# RPi_BUS-Controller_V1_0.net
KiCad netlist of a schematic drawn in EAGLE
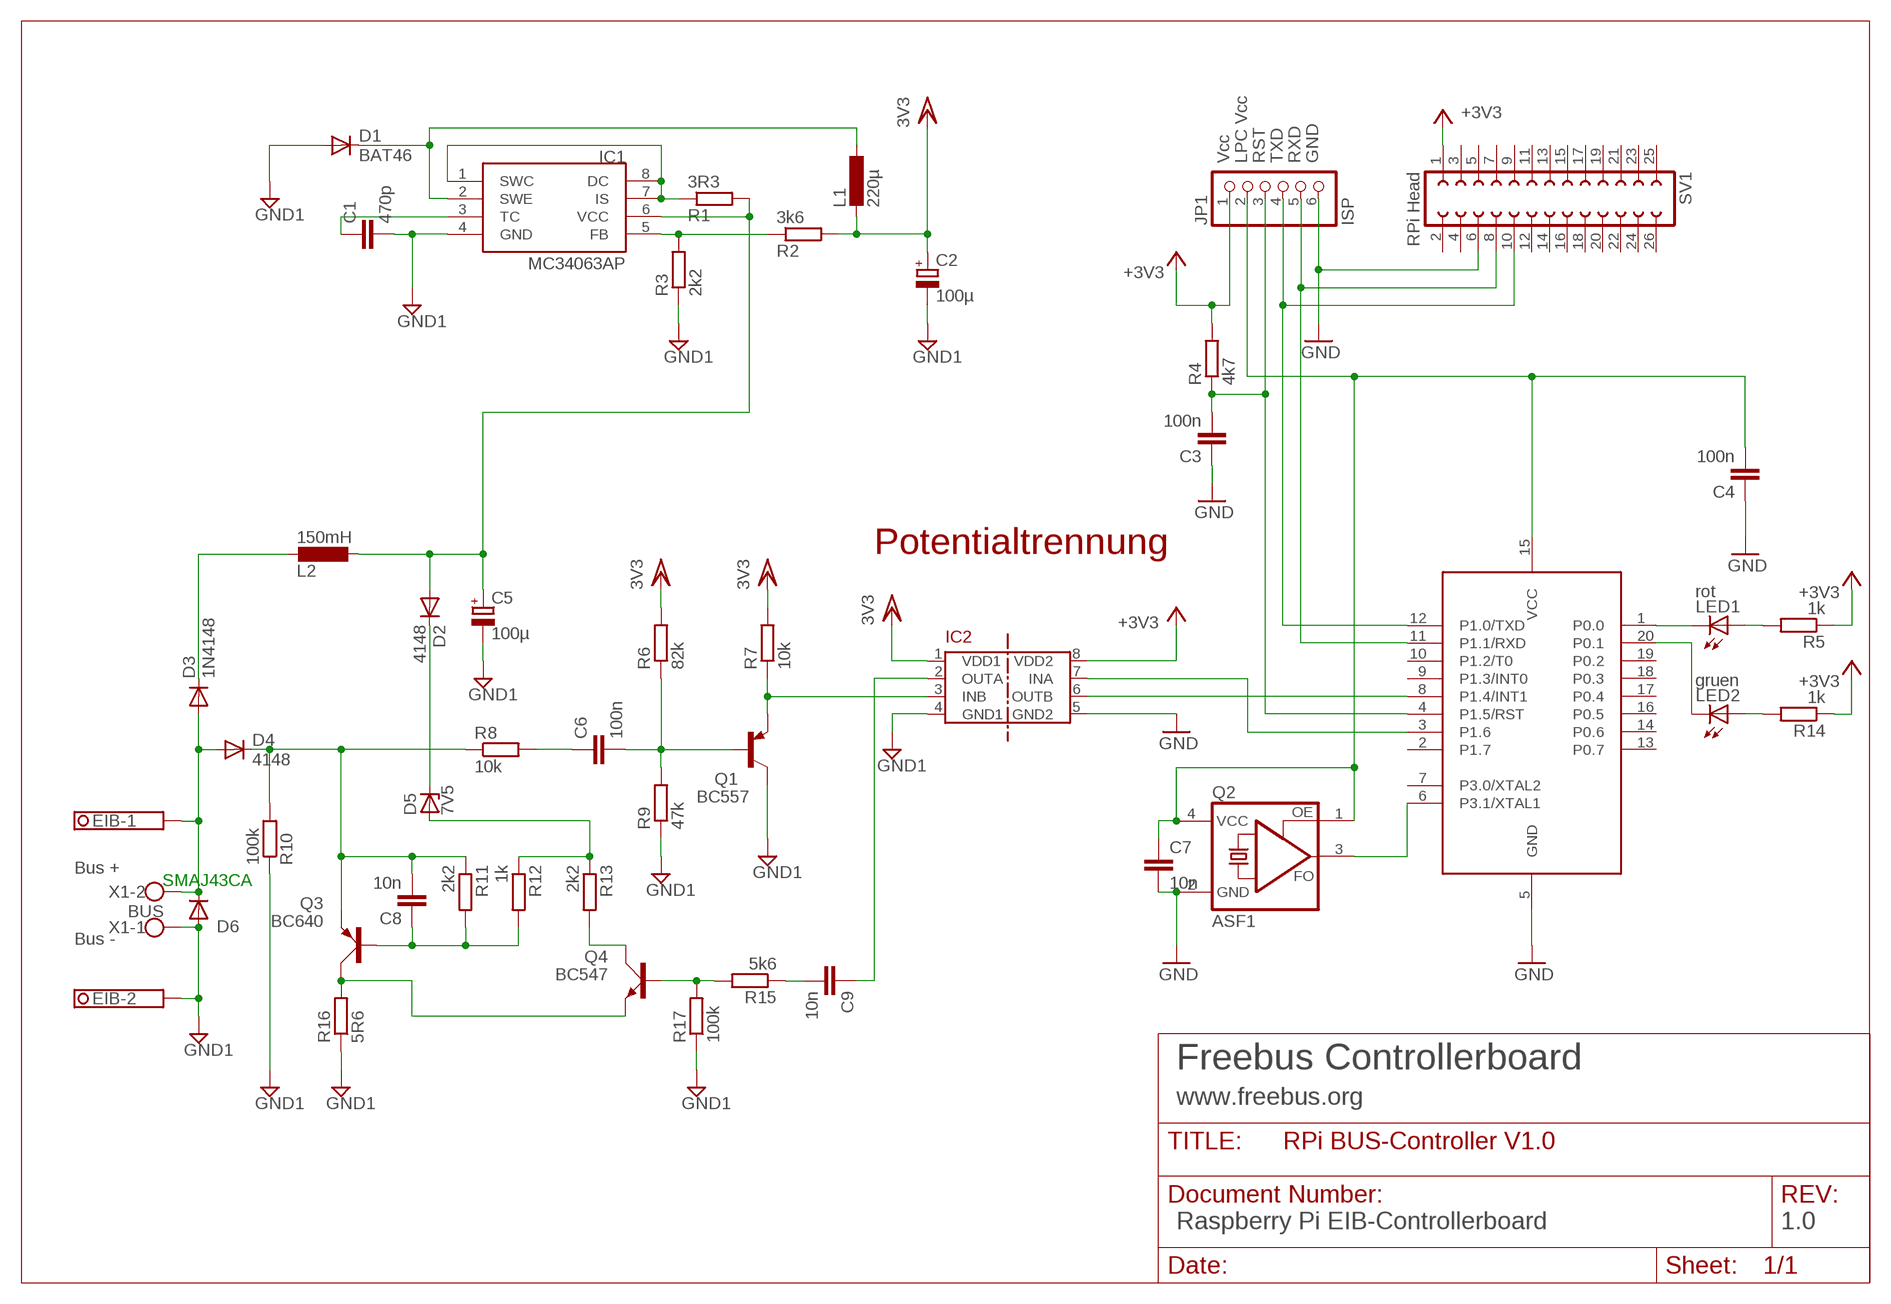
[diagram p0: schematic, sheet 1]

(export (version "E")
  (design (tool "Eeschema 10.0.6"))
  (components
    (comp (ref "C1")
      (value "470p")
      (footprint "eagle-import:C025-024X044")
      (libsource (lib "eagle-import") (part "C-EU025-024X044"))
    )
    (comp (ref "C2")
      (value "100µ")
      (footprint "eagle-import:2-5X11")
      (libsource (lib "eagle-import") (part "RCL_C_EU_H2-5X11"))
    )
    (comp (ref "C3")
      (value "100n")
      (footprint "eagle-import:C025-024X044")
      (libsource (lib "eagle-import") (part "C-EU025-024X044"))
    )
    (comp (ref "C4")
      (value "100n")
      (footprint "eagle-import:C025-024X044")
      (libsource (lib "eagle-import") (part "C-EU025-024X044"))
    )
    (comp (ref "C5")
      (value "100µ")
      (footprint "eagle-import:3,5-8X13")
      (libsource (lib "eagle-import") (part "RCL_C_EU_H3,5-8X13"))
    )
    (comp (ref "C6")
      (value "100n")
      (footprint "eagle-import:C025-024X044")
      (libsource (lib "eagle-import") (part "C-EU025-024X044"))
    )
    (comp (ref "C7")
      (value "10n")
      (footprint "eagle-import:C025-024X044")
      (libsource (lib "eagle-import") (part "C-EU025-024X044"))
    )
    (comp (ref "C8")
      (value "10n")
      (footprint "eagle-import:C025-024X044")
      (libsource (lib "eagle-import") (part "C-EU025-024X044"))
    )
    (comp (ref "C9")
      (value "10n")
      (footprint "eagle-import:C025-024X044")
      (libsource (lib "eagle-import") (part "C-EU025-024X044"))
    )
    (comp (ref "D1")
      (value "BAT46")
      (footprint "eagle-import:DO35-7")
      (libsource (lib "eagle-import") (part "1N4148DO35-7"))
    )
    (comp (ref "D2")
      (value "4148")
      (footprint "eagle-import:DO35-7")
      (libsource (lib "eagle-import") (part "1N4148DO35-7"))
    )
    (comp (ref "D3")
      (value "1N4148")
      (footprint "eagle-import:DO35-7")
      (libsource (lib "eagle-import") (part "1N4148DO35-7"))
    )
    (comp (ref "D4")
      (value "4148")
      (footprint "eagle-import:DO35-7")
      (libsource (lib "eagle-import") (part "1N4148DO35-7"))
    )
    (comp (ref "D5")
      (value "7V5")
      (footprint "eagle-import:DO35Z7")
      (libsource (lib "eagle-import") (part "ZPD{dblquote}"))
    )
    (comp (ref "D6")
      (value "SMAJ43CA")
      (footprint "eagle-import:SMB")
      (libsource (lib "eagle-import") (part "D-SMB"))
    )
    (comp (ref "EIB")
      (value "1751248")
      (footprint "eagle-import:1751248")
      (libsource (lib "eagle-import") (part "1751248"))
    )
    (comp (ref "IC1")
      (value "MC34063AP")
      (footprint "eagle-import:DIL08")
      (libsource (lib "eagle-import") (part "MC34063AP"))
    )
    (comp (ref "IC2")
      (value "ADUM1201")
      (footprint "eagle-import:SO8")
      (libsource (lib "eagle-import") (part "ADUM1201"))
    )
    (comp (ref "IC3")
      (value "89LPC922")
      (footprint "eagle-import:DIL20")
      (libsource (lib "eagle-import") (part "89LPC922"))
    )
    (comp (ref "JP1")
      (value "ISP")
      (footprint "eagle-import:1X06")
      (libsource (lib "eagle-import") (part "PINHD-1X6"))
    )
    (comp (ref "L1")
      (value "220µ")
      (footprint "eagle-import:0207_12")
      (libsource (lib "eagle-import") (part "L-EU0207/12"))
    )
    (comp (ref "L2")
      (value "150mH")
      (footprint "eagle-import:RCL_11PH")
      (libsource (lib "eagle-import") (part "RCL_L-11P11PH"))
    )
    (comp (ref "LED1")
      (value "rot")
      (footprint "eagle-import:LED3MM")
      (libsource (lib "eagle-import") (part "LED3MM"))
    )
    (comp (ref "LED2")
      (value "gruen")
      (footprint "eagle-import:LED3MM")
      (libsource (lib "eagle-import") (part "LED3MM"))
    )
    (comp (ref "Q1")
      (value "BC557")
      (footprint "eagle-import:TO92")
      (libsource (lib "eagle-import") (part "BC557"))
    )
    (comp (ref "Q2")
      (value "ASF1")
      (footprint "eagle-import:ASF")
      (libsource (lib "eagle-import") (part "ASF1"))
    )
    (comp (ref "Q3")
      (value "BC640")
      (footprint "eagle-import:SOT54D")
      (libsource (lib "eagle-import") (part "BC640"))
    )
    (comp (ref "Q4")
      (value "BC547")
      (footprint "eagle-import:SOT54A")
      (libsource (lib "eagle-import") (part "BC547"))
    )
    (comp (ref "R1")
      (value "3R3")
      (footprint "eagle-import:0207_7")
      (libsource (lib "eagle-import") (part "R-EU_0207/7"))
    )
    (comp (ref "R2")
      (value "3k6")
      (footprint "eagle-import:0207_7")
      (libsource (lib "eagle-import") (part "R-EU_0207/7"))
    )
    (comp (ref "R3")
      (value "2k2")
      (footprint "eagle-import:0207_7")
      (libsource (lib "eagle-import") (part "R-EU_0207/7"))
    )
    (comp (ref "R4")
      (value "4k7")
      (footprint "eagle-import:0207_7")
      (libsource (lib "eagle-import") (part "R-EU_0207/7"))
    )
    (comp (ref "R5")
      (value "1k")
      (footprint "eagle-import:0207_7")
      (libsource (lib "eagle-import") (part "R-EU_0207/7"))
    )
    (comp (ref "R6")
      (value "82k")
      (footprint "eagle-import:0207_7")
      (libsource (lib "eagle-import") (part "R-EU_0207/7"))
    )
    (comp (ref "R7")
      (value "10k")
      (footprint "eagle-import:0207_7")
      (libsource (lib "eagle-import") (part "R-EU_0207/7"))
    )
    (comp (ref "R8")
      (value "10k")
      (footprint "eagle-import:0207_7")
      (libsource (lib "eagle-import") (part "R-EU_0207/7"))
    )
    (comp (ref "R9")
      (value "47k")
      (footprint "eagle-import:0207_7")
      (libsource (lib "eagle-import") (part "R-EU_0207/7"))
    )
    (comp (ref "R10")
      (value "100k")
      (footprint "eagle-import:0207_7")
      (libsource (lib "eagle-import") (part "R-EU_0207/7"))
    )
    (comp (ref "R11")
      (value "2k2")
      (footprint "eagle-import:0207_7")
      (libsource (lib "eagle-import") (part "R-EU_0207/7"))
    )
    (comp (ref "R12")
      (value "1k")
      (footprint "eagle-import:0207_7")
      (libsource (lib "eagle-import") (part "R-EU_0207/7"))
    )
    (comp (ref "R13")
      (value "2k2")
      (footprint "eagle-import:0207_7")
      (libsource (lib "eagle-import") (part "R-EU_0207/7"))
    )
    (comp (ref "R14")
      (value "1k")
      (footprint "eagle-import:0207_7")
      (libsource (lib "eagle-import") (part "R-EU_0207/7"))
    )
    (comp (ref "R15")
      (value "5k6")
      (footprint "eagle-import:0207_7")
      (libsource (lib "eagle-import") (part "R-EU_0207/7"))
    )
    (comp (ref "R16")
      (value "5R6")
      (footprint "eagle-import:0207_7")
      (libsource (lib "eagle-import") (part "R-EU_0207/7"))
    )
    (comp (ref "R17")
      (value "100k")
      (footprint "eagle-import:0207_7")
      (libsource (lib "eagle-import") (part "R-EU_0207/7"))
    )
    (comp (ref "SV1")
      (value "RPi Head")
      (footprint "eagle-import:FE13-2")
      (libsource (lib "eagle-import") (part "FE13-2"))
    )
    (comp (ref "X1")
      (value "BUS")
      (footprint "eagle-import:W237-132")
      (libsource (lib "eagle-import") (part "W237-02P"))
    )
  )
  (nets
    (net (code "1") (name "+3V3") (class "Default")
      (node (ref "IC2") (pin "8") (pinfunction "VDD2_8") (pintype "power_in"))
      (node (ref "JP1") (pin "1") (pinfunction "1_1") (pintype "passive"))
      (node (ref "R14") (pin "1") (pinfunction "1_1") (pintype "passive"))
      (node (ref "R4") (pin "2") (pinfunction "2_2") (pintype "passive"))
      (node (ref "R5") (pin "1") (pinfunction "1_1") (pintype "passive"))
      (node (ref "SV1") (pin "1") (pinfunction "1_1") (pintype "passive"))
    )
    (net (code "2") (name "3V3") (class "Default")
      (node (ref "C2") (pin "+") (pinfunction "+_+") (pintype "passive"))
      (node (ref "IC2") (pin "1") (pinfunction "VDD1_1") (pintype "power_in"))
      (node (ref "L1") (pin "2") (pinfunction "2_2") (pintype "passive"))
      (node (ref "R2") (pin "2") (pinfunction "2_2") (pintype "passive"))
      (node (ref "R6") (pin "2") (pinfunction "2_2") (pintype "passive"))
      (node (ref "R7") (pin "2") (pinfunction "2_2") (pintype "passive"))
    )
    (net (code "3") (name "GND") (class "Default")
      (node (ref "C3") (pin "1") (pinfunction "1_1") (pintype "passive"))
      (node (ref "C4") (pin "1") (pinfunction "1_1") (pintype "passive"))
      (node (ref "C7") (pin "2") (pinfunction "2_2") (pintype "passive"))
      (node (ref "IC2") (pin "5") (pinfunction "GND2_5") (pintype "power_in"))
      (node (ref "IC3") (pin "5") (pinfunction "GND_5") (pintype "bidirectional"))
      (node (ref "JP1") (pin "6") (pinfunction "6_6") (pintype "passive"))
      (node (ref "Q2") (pin "2") (pinfunction "GND_2") (pintype "power_in"))
      (node (ref "SV1") (pin "6") (pinfunction "6_6") (pintype "passive"))
    )
    (net (code "4") (name "GND1") (class "Default")
      (node (ref "C1") (pin "2") (pinfunction "2_2") (pintype "passive"))
      (node (ref "C2") (pin "-") (pinfunction "-_-") (pintype "passive"))
      (node (ref "C5") (pin "-") (pinfunction "-_-") (pintype "passive"))
      (node (ref "D1") (pin "A") (pinfunction "A_A") (pintype "passive"))
      (node (ref "D6") (pin "2") (pinfunction "A_2") (pintype "passive"))
      (node (ref "EIB") (pin "2") (pinfunction "K_2") (pintype "passive"))
      (node (ref "IC1") (pin "4") (pinfunction "GND_4") (pintype "passive"))
      (node (ref "IC2") (pin "4") (pinfunction "GND1_4") (pintype "power_in"))
      (node (ref "Q1") (pin "3") (pinfunction "C_3") (pintype "passive"))
      (node (ref "R10") (pin "1") (pinfunction "1_1") (pintype "passive"))
      (node (ref "R16") (pin "1") (pinfunction "1_1") (pintype "passive"))
      (node (ref "R17") (pin "1") (pinfunction "1_1") (pintype "passive"))
      (node (ref "R3") (pin "1") (pinfunction "1_1") (pintype "passive"))
      (node (ref "R9") (pin "1") (pinfunction "1_1") (pintype "passive"))
      (node (ref "X1") (pin "1") (pinfunction "KL_1") (pintype "passive"))
    )
    (net (code "5") (name "Net-(C6-Pad1)") (class "Default")
      (node (ref "C6") (pin "1") (pinfunction "1_1") (pintype "passive"))
      (node (ref "R8") (pin "2") (pinfunction "2_2") (pintype "passive"))
    )
    (net (code "6") (name "Net-(C8-Pad1)") (class "Default")
      (node (ref "C8") (pin "1") (pinfunction "1_1") (pintype "passive"))
      (node (ref "Q3") (pin "B") (pinfunction "B_B") (pintype "passive"))
      (node (ref "R11") (pin "2") (pinfunction "2_2") (pintype "passive"))
      (node (ref "R12") (pin "2") (pinfunction "2_2") (pintype "passive"))
    )
    (net (code "7") (name "Net-(C8-Pad2)") (class "Default")
      (node (ref "C8") (pin "2") (pinfunction "2_2") (pintype "passive"))
      (node (ref "D4") (pin "C") (pinfunction "C_C") (pintype "passive"))
      (node (ref "Q3") (pin "E") (pinfunction "E_E") (pintype "passive"))
      (node (ref "R10") (pin "2") (pinfunction "2_2") (pintype "passive"))
      (node (ref "R11") (pin "1") (pinfunction "1_1") (pintype "passive"))
      (node (ref "R8") (pin "1") (pinfunction "1_1") (pintype "passive"))
    )
    (net (code "8") (name "Net-(C9-Pad2)") (class "Default")
      (node (ref "C9") (pin "2") (pinfunction "2_2") (pintype "passive"))
      (node (ref "R15") (pin "1") (pinfunction "1_1") (pintype "passive"))
    )
    (net (code "9") (name "Net-(D2-PadC)") (class "Default")
      (node (ref "D2") (pin "C") (pinfunction "C_C") (pintype "passive"))
      (node (ref "D5") (pin "C") (pinfunction "C_C") (pintype "passive"))
    )
    (net (code "10") (name "Net-(D5-PadA)") (class "Default")
      (node (ref "D5") (pin "A") (pinfunction "A_A") (pintype "passive"))
      (node (ref "R12") (pin "1") (pinfunction "1_1") (pintype "passive"))
      (node (ref "R13") (pin "1") (pinfunction "1_1") (pintype "passive"))
    )
    (net (code "11") (name "Net-(D6-C)") (class "Default")
      (node (ref "D3") (pin "A") (pinfunction "A_A") (pintype "passive"))
      (node (ref "D4") (pin "A") (pinfunction "A_A") (pintype "passive"))
      (node (ref "D6") (pin "1") (pinfunction "C_1") (pintype "passive"))
      (node (ref "EIB") (pin "1") (pinfunction "K_1") (pintype "passive"))
      (node (ref "X1") (pin "2") (pinfunction "KL_2") (pintype "passive"))
    )
    (net (code "12") (name "Net-(IC1-DC)") (class "Default")
      (node (ref "IC1") (pin "1") (pinfunction "SWC_1") (pintype "passive"))
      (node (ref "IC1") (pin "7") (pinfunction "IS_7") (pintype "passive"))
      (node (ref "IC1") (pin "8") (pinfunction "DC_8") (pintype "passive"))
      (node (ref "R1") (pin "1") (pinfunction "1_1") (pintype "passive"))
    )
    (net (code "13") (name "Net-(IC1-FB)") (class "Default")
      (node (ref "IC1") (pin "5") (pinfunction "FB_5") (pintype "passive"))
      (node (ref "R2") (pin "1") (pinfunction "1_1") (pintype "passive"))
      (node (ref "R3") (pin "2") (pinfunction "2_2") (pintype "passive"))
    )
    (net (code "14") (name "Net-(IC1-SWE)") (class "Default")
      (node (ref "D1") (pin "C") (pinfunction "C_C") (pintype "passive"))
      (node (ref "IC1") (pin "2") (pinfunction "SWE_2") (pintype "passive"))
      (node (ref "L1") (pin "1") (pinfunction "1_1") (pintype "passive"))
    )
    (net (code "15") (name "Net-(IC1-TC)") (class "Default")
      (node (ref "C1") (pin "1") (pinfunction "1_1") (pintype "passive"))
      (node (ref "IC1") (pin "3") (pinfunction "TC_3") (pintype "passive"))
    )
    (net (code "16") (name "Net-(IC1-VCC)") (class "Default")
      (node (ref "C5") (pin "+") (pinfunction "+_+") (pintype "passive"))
      (node (ref "D2") (pin "A") (pinfunction "A_A") (pintype "passive"))
      (node (ref "IC1") (pin "6") (pinfunction "VCC_6") (pintype "passive"))
      (node (ref "L2") (pin "P$1") (pinfunction "1_P$1") (pintype "passive"))
      (node (ref "R1") (pin "2") (pinfunction "2_2") (pintype "passive"))
    )
    (net (code "17") (name "Net-(IC2-INA)") (class "Default")
      (node (ref "IC2") (pin "7") (pinfunction "INA_7") (pintype "input"))
      (node (ref "IC3") (pin "3") (pinfunction "P1.6_3") (pintype "bidirectional"))
    )
    (net (code "18") (name "Net-(IC2-INB)") (class "Default")
      (node (ref "IC2") (pin "3") (pinfunction "INB_3") (pintype "input"))
      (node (ref "Q1") (pin "1") (pinfunction "E_1") (pintype "passive"))
      (node (ref "R7") (pin "1") (pinfunction "1_1") (pintype "passive"))
    )
    (net (code "19") (name "Net-(IC2-OUTA)") (class "Default")
      (node (ref "C9") (pin "1") (pinfunction "1_1") (pintype "passive"))
      (node (ref "IC2") (pin "2") (pinfunction "OUTA_2") (pintype "output"))
    )
    (net (code "20") (name "Net-(IC2-OUTB)") (class "Default")
      (node (ref "IC2") (pin "6") (pinfunction "OUTB_6") (pintype "output"))
      (node (ref "IC3") (pin "8") (pinfunction "P1.4/INT1_8") (pintype "bidirectional"))
    )
    (net (code "21") (name "Net-(IC3-P0.0)") (class "Default")
      (node (ref "IC3") (pin "1") (pinfunction "P0.0_1") (pintype "bidirectional"))
      (node (ref "LED1") (pin "K") (pinfunction "C_K") (pintype "passive"))
    )
    (net (code "22") (name "Net-(IC3-P0.1)") (class "Default")
      (node (ref "IC3") (pin "20") (pinfunction "P0.1_20") (pintype "bidirectional"))
      (node (ref "LED2") (pin "K") (pinfunction "C_K") (pintype "passive"))
    )
    (net (code "23") (name "Net-(IC3-P1.0{slash}TXD)") (class "Default")
      (node (ref "IC3") (pin "12") (pinfunction "P1.0/TXD_12") (pintype "bidirectional"))
      (node (ref "JP1") (pin "4") (pinfunction "4_4") (pintype "passive"))
      (node (ref "SV1") (pin "10") (pinfunction "10_10") (pintype "passive"))
    )
    (net (code "24") (name "Net-(IC3-P1.1{slash}RXD)") (class "Default")
      (node (ref "IC3") (pin "11") (pinfunction "P1.1/RXD_11") (pintype "bidirectional"))
      (node (ref "JP1") (pin "5") (pinfunction "5_5") (pintype "passive"))
      (node (ref "SV1") (pin "8") (pinfunction "8_8") (pintype "passive"))
    )
    (net (code "25") (name "Net-(IC3-P1.5{slash}RST)") (class "Default")
      (node (ref "C3") (pin "2") (pinfunction "2_2") (pintype "passive"))
      (node (ref "IC3") (pin "4") (pinfunction "P1.5/RST_4") (pintype "bidirectional"))
      (node (ref "JP1") (pin "3") (pinfunction "3_3") (pintype "passive"))
      (node (ref "R4") (pin "1") (pinfunction "1_1") (pintype "passive"))
    )
    (net (code "26") (name "Net-(IC3-P3.1{slash}XTAL1)") (class "Default")
      (node (ref "IC3") (pin "6") (pinfunction "P3.1/XTAL1_6") (pintype "bidirectional"))
      (node (ref "Q2") (pin "3") (pinfunction "FO_3") (pintype "output"))
    )
    (net (code "27") (name "Net-(IC3-VCC)") (class "Default")
      (node (ref "C4") (pin "2") (pinfunction "2_2") (pintype "passive"))
      (node (ref "C7") (pin "1") (pinfunction "1_1") (pintype "passive"))
      (node (ref "IC3") (pin "15") (pinfunction "VCC_15") (pintype "bidirectional"))
      (node (ref "JP1") (pin "2") (pinfunction "2_2") (pintype "passive"))
      (node (ref "Q2") (pin "1") (pinfunction "OE_1") (pintype "input"))
      (node (ref "Q2") (pin "4") (pinfunction "VCC_4") (pintype "power_in"))
    )
    (net (code "28") (name "Net-(L2-2)") (class "Default")
      (node (ref "D3") (pin "C") (pinfunction "C_C") (pintype "passive"))
      (node (ref "L2") (pin "P$2") (pinfunction "2_P$2") (pintype "passive"))
    )
    (net (code "29") (name "Net-(LED1-PadA)") (class "Default")
      (node (ref "LED1") (pin "A") (pinfunction "A_A") (pintype "passive"))
      (node (ref "R5") (pin "2") (pinfunction "2_2") (pintype "passive"))
    )
    (net (code "30") (name "Net-(LED2-PadA)") (class "Default")
      (node (ref "LED2") (pin "A") (pinfunction "A_A") (pintype "passive"))
      (node (ref "R14") (pin "2") (pinfunction "2_2") (pintype "passive"))
    )
    (net (code "31") (name "Net-(Q1-B)") (class "Default")
      (node (ref "C6") (pin "2") (pinfunction "2_2") (pintype "passive"))
      (node (ref "Q1") (pin "2") (pinfunction "B_2") (pintype "passive"))
      (node (ref "R6") (pin "1") (pinfunction "1_1") (pintype "passive"))
      (node (ref "R9") (pin "2") (pinfunction "2_2") (pintype "passive"))
    )
    (net (code "32") (name "Net-(Q3-PadC)") (class "Default")
      (node (ref "Q3") (pin "C") (pinfunction "C_C") (pintype "passive"))
      (node (ref "Q4") (pin "E") (pinfunction "E_E") (pintype "passive"))
      (node (ref "R16") (pin "2") (pinfunction "2_2") (pintype "passive"))
    )
    (net (code "33") (name "Net-(Q4-PadB)") (class "Default")
      (node (ref "Q4") (pin "B") (pinfunction "B_B") (pintype "passive"))
      (node (ref "R15") (pin "2") (pinfunction "2_2") (pintype "passive"))
      (node (ref "R17") (pin "2") (pinfunction "2_2") (pintype "passive"))
    )
    (net (code "34") (name "Net-(Q4-PadC)") (class "Default")
      (node (ref "Q4") (pin "C") (pinfunction "C_C") (pintype "passive"))
      (node (ref "R13") (pin "2") (pinfunction "2_2") (pintype "passive"))
    )
    (net (code "35") (name "unconnected-(IC3-P0.2-Pad19)") (class "Default")
      (node (ref "IC3") (pin "19") (pinfunction "P0.2_19") (pintype "bidirectional"))
    )
    (net (code "36") (name "unconnected-(IC3-P0.3-Pad18)") (class "Default")
      (node (ref "IC3") (pin "18") (pinfunction "P0.3_18") (pintype "bidirectional"))
    )
    (net (code "37") (name "unconnected-(IC3-P0.4-Pad17)") (class "Default")
      (node (ref "IC3") (pin "17") (pinfunction "P0.4_17") (pintype "bidirectional"))
    )
    (net (code "38") (name "unconnected-(IC3-P0.5-Pad16)") (class "Default")
      (node (ref "IC3") (pin "16") (pinfunction "P0.5_16") (pintype "bidirectional"))
    )
    (net (code "39") (name "unconnected-(IC3-P0.6-Pad14)") (class "Default")
      (node (ref "IC3") (pin "14") (pinfunction "P0.6_14") (pintype "bidirectional"))
    )
    (net (code "40") (name "unconnected-(IC3-P0.7-Pad13)") (class "Default")
      (node (ref "IC3") (pin "13") (pinfunction "P0.7_13") (pintype "bidirectional"))
    )
    (net (code "41") (name "unconnected-(IC3-P1.2{slash}T0-Pad10)") (class "Default")
      (node (ref "IC3") (pin "10") (pinfunction "P1.2/T0_10") (pintype "bidirectional"))
    )
    (net (code "42") (name "unconnected-(IC3-P1.3{slash}INT0-Pad9)") (class "Default")
      (node (ref "IC3") (pin "9") (pinfunction "P1.3/INT0_9") (pintype "bidirectional"))
    )
    (net (code "43") (name "unconnected-(IC3-P1.7-Pad2)") (class "Default")
      (node (ref "IC3") (pin "2") (pinfunction "P1.7_2") (pintype "bidirectional"))
    )
    (net (code "44") (name "unconnected-(IC3-P3.0{slash}XTAL2-Pad7)") (class "Default")
      (node (ref "IC3") (pin "7") (pinfunction "P3.0/XTAL2_7") (pintype "bidirectional"))
    )
    (net (code "45") (name "unconnected-(SV1-Pad2)") (class "Default")
      (node (ref "SV1") (pin "2") (pinfunction "2_2") (pintype "passive"))
    )
    (net (code "46") (name "unconnected-(SV1-Pad3)") (class "Default")
      (node (ref "SV1") (pin "3") (pinfunction "3_3") (pintype "passive"))
    )
    (net (code "47") (name "unconnected-(SV1-Pad4)") (class "Default")
      (node (ref "SV1") (pin "4") (pinfunction "4_4") (pintype "passive"))
    )
    (net (code "48") (name "unconnected-(SV1-Pad5)") (class "Default")
      (node (ref "SV1") (pin "5") (pinfunction "5_5") (pintype "passive"))
    )
    (net (code "49") (name "unconnected-(SV1-Pad7)") (class "Default")
      (node (ref "SV1") (pin "7") (pinfunction "7_7") (pintype "passive"))
    )
    (net (code "50") (name "unconnected-(SV1-Pad9)") (class "Default")
      (node (ref "SV1") (pin "9") (pinfunction "9_9") (pintype "passive"))
    )
    (net (code "51") (name "unconnected-(SV1-Pad11)") (class "Default")
      (node (ref "SV1") (pin "11") (pinfunction "11_11") (pintype "passive"))
    )
    (net (code "52") (name "unconnected-(SV1-Pad12)") (class "Default")
      (node (ref "SV1") (pin "12") (pinfunction "12_12") (pintype "passive"))
    )
    (net (code "53") (name "unconnected-(SV1-Pad13)") (class "Default")
      (node (ref "SV1") (pin "13") (pinfunction "13_13") (pintype "passive"))
    )
    (net (code "54") (name "unconnected-(SV1-Pad14)") (class "Default")
      (node (ref "SV1") (pin "14") (pinfunction "14_14") (pintype "passive"))
    )
    (net (code "55") (name "unconnected-(SV1-Pad15)") (class "Default")
      (node (ref "SV1") (pin "15") (pinfunction "15_15") (pintype "passive"))
    )
    (net (code "56") (name "unconnected-(SV1-Pad16)") (class "Default")
      (node (ref "SV1") (pin "16") (pinfunction "16_16") (pintype "passive"))
    )
    (net (code "57") (name "unconnected-(SV1-Pad17)") (class "Default")
      (node (ref "SV1") (pin "17") (pinfunction "17_17") (pintype "passive"))
    )
    (net (code "58") (name "unconnected-(SV1-Pad18)") (class "Default")
      (node (ref "SV1") (pin "18") (pinfunction "18_18") (pintype "passive"))
    )
    (net (code "59") (name "unconnected-(SV1-Pad19)") (class "Default")
      (node (ref "SV1") (pin "19") (pinfunction "19_19") (pintype "passive"))
    )
    (net (code "60") (name "unconnected-(SV1-Pad20)") (class "Default")
      (node (ref "SV1") (pin "20") (pinfunction "20_20") (pintype "passive"))
    )
    (net (code "61") (name "unconnected-(SV1-Pad21)") (class "Default")
      (node (ref "SV1") (pin "21") (pinfunction "21_21") (pintype "passive"))
    )
    (net (code "62") (name "unconnected-(SV1-Pad22)") (class "Default")
      (node (ref "SV1") (pin "22") (pinfunction "22_22") (pintype "passive"))
    )
    (net (code "63") (name "unconnected-(SV1-Pad23)") (class "Default")
      (node (ref "SV1") (pin "23") (pinfunction "23_23") (pintype "passive"))
    )
    (net (code "64") (name "unconnected-(SV1-Pad24)") (class "Default")
      (node (ref "SV1") (pin "24") (pinfunction "24_24") (pintype "passive"))
    )
    (net (code "65") (name "unconnected-(SV1-Pad25)") (class "Default")
      (node (ref "SV1") (pin "25") (pinfunction "25_25") (pintype "passive"))
    )
    (net (code "66") (name "unconnected-(SV1-Pad26)") (class "Default")
      (node (ref "SV1") (pin "26") (pinfunction "26_26") (pintype "passive"))
    )
  )
)
